# Peltier_Driver.net
KiCad netlist of a schematic drawn in EAGLE
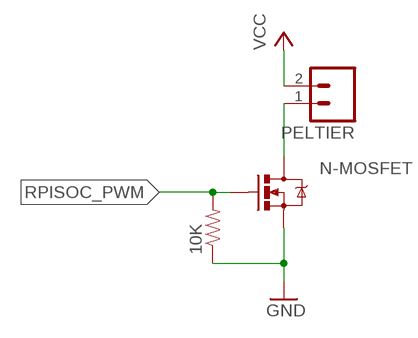
[diagram p0: schematic, sheet 1]

(export (version "E")
  (design (tool "Eeschema 10.0.6"))
  (components
    (comp (ref "10K")
      (value "RESISTOR0402-RES")
      (footprint "eagle-import:0402-RES")
      (libsource (lib "eagle-import") (part "RESISTOR0402-RES"))
    )
    (comp (ref "N-MOSFET")
      (value "MOSFET-NCHANNEL2N7000")
      (footprint "eagle-import:TO-92")
      (libsource (lib "eagle-import") (part "MOSFET-NCHANNEL2N7000"))
    )
    (comp (ref "PELTIER")
      (value "M02-JST-2MM-SMT")
      (footprint "eagle-import:JST-2-SMD")
      (libsource (lib "eagle-import") (part "M02-JST-2MM-SMT"))
    )
  )
  (nets
    (net (code "1") (name "GND") (class "Default")
      (node (ref "10K") (pin "1") (pinfunction "1_1") (pintype "passive"))
      (node (ref "N-MOSFET") (pin "1") (pinfunction "S_1") (pintype "passive"))
    )
    (net (code "2") (name "Net-(N-MOSFET-D)") (class "Default")
      (node (ref "N-MOSFET") (pin "3") (pinfunction "D_3") (pintype "passive"))
      (node (ref "PELTIER") (pin "1") (pinfunction "2_1") (pintype "passive"))
    )
    (net (code "3") (name "RPISOC_PWM") (class "Default")
      (node (ref "10K") (pin "2") (pinfunction "2_2") (pintype "passive"))
      (node (ref "N-MOSFET") (pin "2") (pinfunction "G_2") (pintype "passive"))
    )
    (net (code "4") (name "VCC") (class "Default")
      (node (ref "PELTIER") (pin "2") (pinfunction "1_2") (pintype "passive"))
    )
  )
)
